# Pinduino-Nano-Sys11-adaptor-panalized_2-.net
KiCad netlist of a schematic drawn in EAGLE
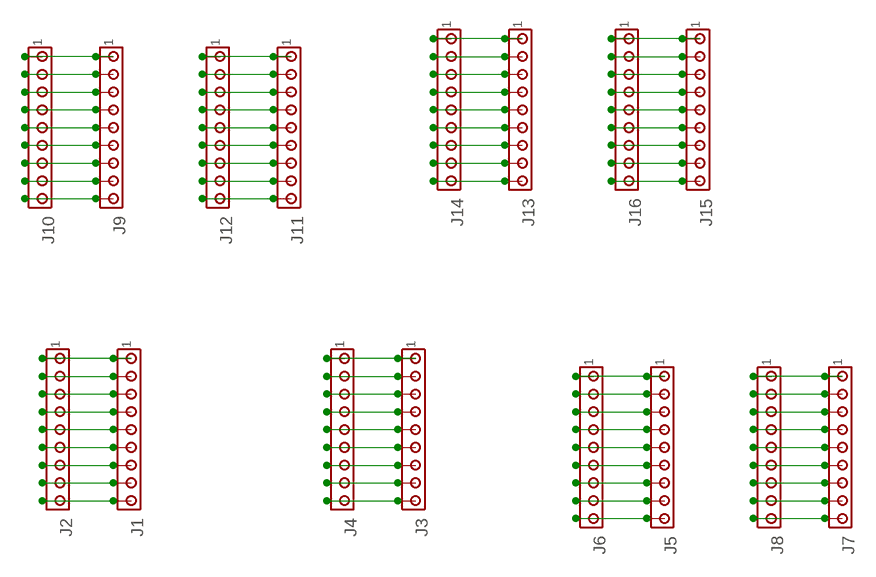
[diagram p0: schematic, sheet 1]

(export (version "E")
  (design (tool "Eeschema 10.0.6"))
  (components
    (comp (ref "J1")
      (value "MTA09-156")
      (footprint "eagle-import:1X9MTA")
      (libsource (lib "eagle-import") (part "MTA09-156"))
    )
    (comp (ref "J2")
      (value "MTA09-156")
      (footprint "eagle-import:1X9MTA")
      (libsource (lib "eagle-import") (part "MTA09-156"))
    )
    (comp (ref "J3")
      (value "MTA09-156")
      (footprint "eagle-import:1X9MTA")
      (libsource (lib "eagle-import") (part "MTA09-156"))
    )
    (comp (ref "J4")
      (value "MTA09-156")
      (footprint "eagle-import:1X9MTA")
      (libsource (lib "eagle-import") (part "MTA09-156"))
    )
    (comp (ref "J5")
      (value "MTA09-156")
      (footprint "eagle-import:1X9MTA")
      (libsource (lib "eagle-import") (part "MTA09-156"))
    )
    (comp (ref "J6")
      (value "MTA09-156")
      (footprint "eagle-import:1X9MTA")
      (libsource (lib "eagle-import") (part "MTA09-156"))
    )
    (comp (ref "J7")
      (value "MTA09-156")
      (footprint "eagle-import:1X9MTA")
      (libsource (lib "eagle-import") (part "MTA09-156"))
    )
    (comp (ref "J8")
      (value "MTA09-156")
      (footprint "eagle-import:1X9MTA")
      (libsource (lib "eagle-import") (part "MTA09-156"))
    )
    (comp (ref "J9")
      (value "MTA09-156")
      (footprint "eagle-import:1X9MTA")
      (libsource (lib "eagle-import") (part "MTA09-156"))
    )
    (comp (ref "J10")
      (value "MTA09-156")
      (footprint "eagle-import:1X9MTA")
      (libsource (lib "eagle-import") (part "MTA09-156"))
    )
    (comp (ref "J11")
      (value "MTA09-156")
      (footprint "eagle-import:1X9MTA")
      (libsource (lib "eagle-import") (part "MTA09-156"))
    )
    (comp (ref "J12")
      (value "MTA09-156")
      (footprint "eagle-import:1X9MTA")
      (libsource (lib "eagle-import") (part "MTA09-156"))
    )
    (comp (ref "J13")
      (value "MTA09-156")
      (footprint "eagle-import:1X9MTA")
      (libsource (lib "eagle-import") (part "MTA09-156"))
    )
    (comp (ref "J14")
      (value "MTA09-156")
      (footprint "eagle-import:1X9MTA")
      (libsource (lib "eagle-import") (part "MTA09-156"))
    )
    (comp (ref "J15")
      (value "MTA09-156")
      (footprint "eagle-import:1X9MTA")
      (libsource (lib "eagle-import") (part "MTA09-156"))
    )
    (comp (ref "J16")
      (value "MTA09-156")
      (footprint "eagle-import:1X9MTA")
      (libsource (lib "eagle-import") (part "MTA09-156"))
    )
  )
  (nets
    (net (code "1") (name "Net-(J1-Pad1)") (class "Default")
      (node (ref "J1") (pin "1") (pinfunction "1_1") (pintype "passive"))
      (node (ref "J2") (pin "1") (pinfunction "1_1") (pintype "passive"))
    )
    (net (code "2") (name "Net-(J1-Pad2)") (class "Default")
      (node (ref "J1") (pin "2") (pinfunction "2_2") (pintype "passive"))
      (node (ref "J2") (pin "2") (pinfunction "2_2") (pintype "passive"))
    )
    (net (code "3") (name "Net-(J1-Pad3)") (class "Default")
      (node (ref "J1") (pin "3") (pinfunction "3_3") (pintype "passive"))
      (node (ref "J2") (pin "3") (pinfunction "3_3") (pintype "passive"))
    )
    (net (code "4") (name "Net-(J1-Pad4)") (class "Default")
      (node (ref "J1") (pin "4") (pinfunction "4_4") (pintype "passive"))
      (node (ref "J2") (pin "4") (pinfunction "4_4") (pintype "passive"))
    )
    (net (code "5") (name "Net-(J1-Pad5)") (class "Default")
      (node (ref "J1") (pin "5") (pinfunction "5_5") (pintype "passive"))
      (node (ref "J2") (pin "5") (pinfunction "5_5") (pintype "passive"))
    )
    (net (code "6") (name "Net-(J1-Pad6)") (class "Default")
      (node (ref "J1") (pin "6") (pinfunction "6_6") (pintype "passive"))
      (node (ref "J2") (pin "6") (pinfunction "6_6") (pintype "passive"))
    )
    (net (code "7") (name "Net-(J1-Pad7)") (class "Default")
      (node (ref "J1") (pin "7") (pinfunction "7_7") (pintype "passive"))
      (node (ref "J2") (pin "7") (pinfunction "7_7") (pintype "passive"))
    )
    (net (code "8") (name "Net-(J1-Pad8)") (class "Default")
      (node (ref "J1") (pin "8") (pinfunction "8_8") (pintype "passive"))
      (node (ref "J2") (pin "8") (pinfunction "8_8") (pintype "passive"))
    )
    (net (code "9") (name "Net-(J1-Pad9)") (class "Default")
      (node (ref "J1") (pin "9") (pinfunction "9_9") (pintype "passive"))
      (node (ref "J2") (pin "9") (pinfunction "9_9") (pintype "passive"))
    )
    (net (code "10") (name "Net-(J3-Pad1)") (class "Default")
      (node (ref "J3") (pin "1") (pinfunction "1_1") (pintype "passive"))
      (node (ref "J4") (pin "1") (pinfunction "1_1") (pintype "passive"))
    )
    (net (code "11") (name "Net-(J3-Pad2)") (class "Default")
      (node (ref "J3") (pin "2") (pinfunction "2_2") (pintype "passive"))
      (node (ref "J4") (pin "2") (pinfunction "2_2") (pintype "passive"))
    )
    (net (code "12") (name "Net-(J3-Pad3)") (class "Default")
      (node (ref "J3") (pin "3") (pinfunction "3_3") (pintype "passive"))
      (node (ref "J4") (pin "3") (pinfunction "3_3") (pintype "passive"))
    )
    (net (code "13") (name "Net-(J3-Pad4)") (class "Default")
      (node (ref "J3") (pin "4") (pinfunction "4_4") (pintype "passive"))
      (node (ref "J4") (pin "4") (pinfunction "4_4") (pintype "passive"))
    )
    (net (code "14") (name "Net-(J3-Pad5)") (class "Default")
      (node (ref "J3") (pin "5") (pinfunction "5_5") (pintype "passive"))
      (node (ref "J4") (pin "5") (pinfunction "5_5") (pintype "passive"))
    )
    (net (code "15") (name "Net-(J3-Pad6)") (class "Default")
      (node (ref "J3") (pin "6") (pinfunction "6_6") (pintype "passive"))
      (node (ref "J4") (pin "6") (pinfunction "6_6") (pintype "passive"))
    )
    (net (code "16") (name "Net-(J3-Pad7)") (class "Default")
      (node (ref "J3") (pin "7") (pinfunction "7_7") (pintype "passive"))
      (node (ref "J4") (pin "7") (pinfunction "7_7") (pintype "passive"))
    )
    (net (code "17") (name "Net-(J3-Pad8)") (class "Default")
      (node (ref "J3") (pin "8") (pinfunction "8_8") (pintype "passive"))
      (node (ref "J4") (pin "8") (pinfunction "8_8") (pintype "passive"))
    )
    (net (code "18") (name "Net-(J3-Pad9)") (class "Default")
      (node (ref "J3") (pin "9") (pinfunction "9_9") (pintype "passive"))
      (node (ref "J4") (pin "9") (pinfunction "9_9") (pintype "passive"))
    )
    (net (code "19") (name "Net-(J5-Pad1)") (class "Default")
      (node (ref "J5") (pin "1") (pinfunction "1_1") (pintype "passive"))
      (node (ref "J6") (pin "1") (pinfunction "1_1") (pintype "passive"))
    )
    (net (code "20") (name "Net-(J5-Pad2)") (class "Default")
      (node (ref "J5") (pin "2") (pinfunction "2_2") (pintype "passive"))
      (node (ref "J6") (pin "2") (pinfunction "2_2") (pintype "passive"))
    )
    (net (code "21") (name "Net-(J5-Pad3)") (class "Default")
      (node (ref "J5") (pin "3") (pinfunction "3_3") (pintype "passive"))
      (node (ref "J6") (pin "3") (pinfunction "3_3") (pintype "passive"))
    )
    (net (code "22") (name "Net-(J5-Pad4)") (class "Default")
      (node (ref "J5") (pin "4") (pinfunction "4_4") (pintype "passive"))
      (node (ref "J6") (pin "4") (pinfunction "4_4") (pintype "passive"))
    )
    (net (code "23") (name "Net-(J5-Pad5)") (class "Default")
      (node (ref "J5") (pin "5") (pinfunction "5_5") (pintype "passive"))
      (node (ref "J6") (pin "5") (pinfunction "5_5") (pintype "passive"))
    )
    (net (code "24") (name "Net-(J5-Pad6)") (class "Default")
      (node (ref "J5") (pin "6") (pinfunction "6_6") (pintype "passive"))
      (node (ref "J6") (pin "6") (pinfunction "6_6") (pintype "passive"))
    )
    (net (code "25") (name "Net-(J5-Pad7)") (class "Default")
      (node (ref "J5") (pin "7") (pinfunction "7_7") (pintype "passive"))
      (node (ref "J6") (pin "7") (pinfunction "7_7") (pintype "passive"))
    )
    (net (code "26") (name "Net-(J5-Pad8)") (class "Default")
      (node (ref "J5") (pin "8") (pinfunction "8_8") (pintype "passive"))
      (node (ref "J6") (pin "8") (pinfunction "8_8") (pintype "passive"))
    )
    (net (code "27") (name "Net-(J5-Pad9)") (class "Default")
      (node (ref "J5") (pin "9") (pinfunction "9_9") (pintype "passive"))
      (node (ref "J6") (pin "9") (pinfunction "9_9") (pintype "passive"))
    )
    (net (code "28") (name "Net-(J7-Pad1)") (class "Default")
      (node (ref "J7") (pin "1") (pinfunction "1_1") (pintype "passive"))
      (node (ref "J8") (pin "1") (pinfunction "1_1") (pintype "passive"))
    )
    (net (code "29") (name "Net-(J7-Pad2)") (class "Default")
      (node (ref "J7") (pin "2") (pinfunction "2_2") (pintype "passive"))
      (node (ref "J8") (pin "2") (pinfunction "2_2") (pintype "passive"))
    )
    (net (code "30") (name "Net-(J7-Pad3)") (class "Default")
      (node (ref "J7") (pin "3") (pinfunction "3_3") (pintype "passive"))
      (node (ref "J8") (pin "3") (pinfunction "3_3") (pintype "passive"))
    )
    (net (code "31") (name "Net-(J7-Pad4)") (class "Default")
      (node (ref "J7") (pin "4") (pinfunction "4_4") (pintype "passive"))
      (node (ref "J8") (pin "4") (pinfunction "4_4") (pintype "passive"))
    )
    (net (code "32") (name "Net-(J7-Pad5)") (class "Default")
      (node (ref "J7") (pin "5") (pinfunction "5_5") (pintype "passive"))
      (node (ref "J8") (pin "5") (pinfunction "5_5") (pintype "passive"))
    )
    (net (code "33") (name "Net-(J7-Pad6)") (class "Default")
      (node (ref "J7") (pin "6") (pinfunction "6_6") (pintype "passive"))
      (node (ref "J8") (pin "6") (pinfunction "6_6") (pintype "passive"))
    )
    (net (code "34") (name "Net-(J7-Pad7)") (class "Default")
      (node (ref "J7") (pin "7") (pinfunction "7_7") (pintype "passive"))
      (node (ref "J8") (pin "7") (pinfunction "7_7") (pintype "passive"))
    )
    (net (code "35") (name "Net-(J7-Pad8)") (class "Default")
      (node (ref "J7") (pin "8") (pinfunction "8_8") (pintype "passive"))
      (node (ref "J8") (pin "8") (pinfunction "8_8") (pintype "passive"))
    )
    (net (code "36") (name "Net-(J7-Pad9)") (class "Default")
      (node (ref "J7") (pin "9") (pinfunction "9_9") (pintype "passive"))
      (node (ref "J8") (pin "9") (pinfunction "9_9") (pintype "passive"))
    )
    (net (code "37") (name "Net-(J10-Pad1)") (class "Default")
      (node (ref "J10") (pin "1") (pinfunction "1_1") (pintype "passive"))
      (node (ref "J9") (pin "1") (pinfunction "1_1") (pintype "passive"))
    )
    (net (code "38") (name "Net-(J10-Pad2)") (class "Default")
      (node (ref "J10") (pin "2") (pinfunction "2_2") (pintype "passive"))
      (node (ref "J9") (pin "2") (pinfunction "2_2") (pintype "passive"))
    )
    (net (code "39") (name "Net-(J10-Pad3)") (class "Default")
      (node (ref "J10") (pin "3") (pinfunction "3_3") (pintype "passive"))
      (node (ref "J9") (pin "3") (pinfunction "3_3") (pintype "passive"))
    )
    (net (code "40") (name "Net-(J10-Pad4)") (class "Default")
      (node (ref "J10") (pin "4") (pinfunction "4_4") (pintype "passive"))
      (node (ref "J9") (pin "4") (pinfunction "4_4") (pintype "passive"))
    )
    (net (code "41") (name "Net-(J10-Pad5)") (class "Default")
      (node (ref "J10") (pin "5") (pinfunction "5_5") (pintype "passive"))
      (node (ref "J9") (pin "5") (pinfunction "5_5") (pintype "passive"))
    )
    (net (code "42") (name "Net-(J10-Pad6)") (class "Default")
      (node (ref "J10") (pin "6") (pinfunction "6_6") (pintype "passive"))
      (node (ref "J9") (pin "6") (pinfunction "6_6") (pintype "passive"))
    )
    (net (code "43") (name "Net-(J10-Pad7)") (class "Default")
      (node (ref "J10") (pin "7") (pinfunction "7_7") (pintype "passive"))
      (node (ref "J9") (pin "7") (pinfunction "7_7") (pintype "passive"))
    )
    (net (code "44") (name "Net-(J10-Pad8)") (class "Default")
      (node (ref "J10") (pin "8") (pinfunction "8_8") (pintype "passive"))
      (node (ref "J9") (pin "8") (pinfunction "8_8") (pintype "passive"))
    )
    (net (code "45") (name "Net-(J10-Pad9)") (class "Default")
      (node (ref "J10") (pin "9") (pinfunction "9_9") (pintype "passive"))
      (node (ref "J9") (pin "9") (pinfunction "9_9") (pintype "passive"))
    )
    (net (code "46") (name "Net-(J11-Pad1)") (class "Default")
      (node (ref "J11") (pin "1") (pinfunction "1_1") (pintype "passive"))
      (node (ref "J12") (pin "1") (pinfunction "1_1") (pintype "passive"))
    )
    (net (code "47") (name "Net-(J11-Pad2)") (class "Default")
      (node (ref "J11") (pin "2") (pinfunction "2_2") (pintype "passive"))
      (node (ref "J12") (pin "2") (pinfunction "2_2") (pintype "passive"))
    )
    (net (code "48") (name "Net-(J11-Pad3)") (class "Default")
      (node (ref "J11") (pin "3") (pinfunction "3_3") (pintype "passive"))
      (node (ref "J12") (pin "3") (pinfunction "3_3") (pintype "passive"))
    )
    (net (code "49") (name "Net-(J11-Pad4)") (class "Default")
      (node (ref "J11") (pin "4") (pinfunction "4_4") (pintype "passive"))
      (node (ref "J12") (pin "4") (pinfunction "4_4") (pintype "passive"))
    )
    (net (code "50") (name "Net-(J11-Pad5)") (class "Default")
      (node (ref "J11") (pin "5") (pinfunction "5_5") (pintype "passive"))
      (node (ref "J12") (pin "5") (pinfunction "5_5") (pintype "passive"))
    )
    (net (code "51") (name "Net-(J11-Pad6)") (class "Default")
      (node (ref "J11") (pin "6") (pinfunction "6_6") (pintype "passive"))
      (node (ref "J12") (pin "6") (pinfunction "6_6") (pintype "passive"))
    )
    (net (code "52") (name "Net-(J11-Pad7)") (class "Default")
      (node (ref "J11") (pin "7") (pinfunction "7_7") (pintype "passive"))
      (node (ref "J12") (pin "7") (pinfunction "7_7") (pintype "passive"))
    )
    (net (code "53") (name "Net-(J11-Pad8)") (class "Default")
      (node (ref "J11") (pin "8") (pinfunction "8_8") (pintype "passive"))
      (node (ref "J12") (pin "8") (pinfunction "8_8") (pintype "passive"))
    )
    (net (code "54") (name "Net-(J11-Pad9)") (class "Default")
      (node (ref "J11") (pin "9") (pinfunction "9_9") (pintype "passive"))
      (node (ref "J12") (pin "9") (pinfunction "9_9") (pintype "passive"))
    )
    (net (code "55") (name "Net-(J13-Pad1)") (class "Default")
      (node (ref "J13") (pin "1") (pinfunction "1_1") (pintype "passive"))
      (node (ref "J14") (pin "1") (pinfunction "1_1") (pintype "passive"))
    )
    (net (code "56") (name "Net-(J13-Pad2)") (class "Default")
      (node (ref "J13") (pin "2") (pinfunction "2_2") (pintype "passive"))
      (node (ref "J14") (pin "2") (pinfunction "2_2") (pintype "passive"))
    )
    (net (code "57") (name "Net-(J13-Pad3)") (class "Default")
      (node (ref "J13") (pin "3") (pinfunction "3_3") (pintype "passive"))
      (node (ref "J14") (pin "3") (pinfunction "3_3") (pintype "passive"))
    )
    (net (code "58") (name "Net-(J13-Pad4)") (class "Default")
      (node (ref "J13") (pin "4") (pinfunction "4_4") (pintype "passive"))
      (node (ref "J14") (pin "4") (pinfunction "4_4") (pintype "passive"))
    )
    (net (code "59") (name "Net-(J13-Pad5)") (class "Default")
      (node (ref "J13") (pin "5") (pinfunction "5_5") (pintype "passive"))
      (node (ref "J14") (pin "5") (pinfunction "5_5") (pintype "passive"))
    )
    (net (code "60") (name "Net-(J13-Pad6)") (class "Default")
      (node (ref "J13") (pin "6") (pinfunction "6_6") (pintype "passive"))
      (node (ref "J14") (pin "6") (pinfunction "6_6") (pintype "passive"))
    )
    (net (code "61") (name "Net-(J13-Pad7)") (class "Default")
      (node (ref "J13") (pin "7") (pinfunction "7_7") (pintype "passive"))
      (node (ref "J14") (pin "7") (pinfunction "7_7") (pintype "passive"))
    )
    (net (code "62") (name "Net-(J13-Pad8)") (class "Default")
      (node (ref "J13") (pin "8") (pinfunction "8_8") (pintype "passive"))
      (node (ref "J14") (pin "8") (pinfunction "8_8") (pintype "passive"))
    )
    (net (code "63") (name "Net-(J13-Pad9)") (class "Default")
      (node (ref "J13") (pin "9") (pinfunction "9_9") (pintype "passive"))
      (node (ref "J14") (pin "9") (pinfunction "9_9") (pintype "passive"))
    )
    (net (code "64") (name "Net-(J15-Pad1)") (class "Default")
      (node (ref "J15") (pin "1") (pinfunction "1_1") (pintype "passive"))
      (node (ref "J16") (pin "1") (pinfunction "1_1") (pintype "passive"))
    )
    (net (code "65") (name "Net-(J15-Pad2)") (class "Default")
      (node (ref "J15") (pin "2") (pinfunction "2_2") (pintype "passive"))
      (node (ref "J16") (pin "2") (pinfunction "2_2") (pintype "passive"))
    )
    (net (code "66") (name "Net-(J15-Pad3)") (class "Default")
      (node (ref "J15") (pin "3") (pinfunction "3_3") (pintype "passive"))
      (node (ref "J16") (pin "3") (pinfunction "3_3") (pintype "passive"))
    )
    (net (code "67") (name "Net-(J15-Pad4)") (class "Default")
      (node (ref "J15") (pin "4") (pinfunction "4_4") (pintype "passive"))
      (node (ref "J16") (pin "4") (pinfunction "4_4") (pintype "passive"))
    )
    (net (code "68") (name "Net-(J15-Pad5)") (class "Default")
      (node (ref "J15") (pin "5") (pinfunction "5_5") (pintype "passive"))
      (node (ref "J16") (pin "5") (pinfunction "5_5") (pintype "passive"))
    )
    (net (code "69") (name "Net-(J15-Pad6)") (class "Default")
      (node (ref "J15") (pin "6") (pinfunction "6_6") (pintype "passive"))
      (node (ref "J16") (pin "6") (pinfunction "6_6") (pintype "passive"))
    )
    (net (code "70") (name "Net-(J15-Pad7)") (class "Default")
      (node (ref "J15") (pin "7") (pinfunction "7_7") (pintype "passive"))
      (node (ref "J16") (pin "7") (pinfunction "7_7") (pintype "passive"))
    )
    (net (code "71") (name "Net-(J15-Pad8)") (class "Default")
      (node (ref "J15") (pin "8") (pinfunction "8_8") (pintype "passive"))
      (node (ref "J16") (pin "8") (pinfunction "8_8") (pintype "passive"))
    )
    (net (code "72") (name "Net-(J15-Pad9)") (class "Default")
      (node (ref "J15") (pin "9") (pinfunction "9_9") (pintype "passive"))
      (node (ref "J16") (pin "9") (pinfunction "9_9") (pintype "passive"))
    )
  )
)
